# TemperatureSensor.net
KiCad netlist of a schematic drawn in EAGLE
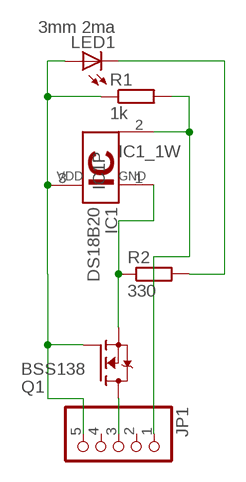
[diagram p0: schematic, sheet 1]

(export (version "E")
  (design (tool "Eeschema 10.0.6"))
  (components
    (comp (ref "IC1")
      (value "DS18B20")
      (footprint "eagle-import:TO92-")
      (libsource (lib "eagle-import") (part "DS18B20"))
    )
    (comp (ref "JP1")
      (value "PINHD-1X5")
      (footprint "eagle-import:1X05")
      (libsource (lib "eagle-import") (part "PINHD-1X5"))
    )
    (comp (ref "LED1")
      (value "3mm 2ma")
      (footprint "eagle-import:LED3MM")
      (fields (field (name "MF") "VISHAY SEMICONDUCTOR"))
      (libsource (lib "eagle-import") (part "TLLY4400"))
    )
    (comp (ref "Q1")
      (value "BSS138")
      (footprint "eagle-import:SOT23")
      (fields (field (name "MF") "Fairchild"))
      (libsource (lib "eagle-import") (part "BSS138"))
    )
    (comp (ref "R1")
      (value "1k")
      (footprint "eagle-import:R1206")
      (libsource (lib "eagle-import") (part "R-EU_R1206"))
    )
    (comp (ref "R2")
      (value "330")
      (footprint "eagle-import:R1206")
      (libsource (lib "eagle-import") (part "R-EU_R1206"))
    )
  )
  (nets
    (net (code "1") (name "Net-(IC1B-GND)") (class "Default")
      (node (ref "IC1") (pin "1") (pinfunction "GND_1") (pintype "power_in"))
      (node (ref "Q1") (pin "2") (pinfunction "S_2") (pintype "passive"))
      (node (ref "R2") (pin "1") (pinfunction "1_1") (pintype "passive"))
    )
    (net (code "2") (name "Net-(IC1B-VDD)") (class "Default")
      (node (ref "IC1") (pin "3") (pinfunction "VDD_3") (pintype "power_in"))
      (node (ref "JP1") (pin "5") (pinfunction "5_5") (pintype "passive"))
      (node (ref "LED1") (pin "A") (pinfunction "A_A") (pintype "passive"))
      (node (ref "Q1") (pin "1") (pinfunction "G_1") (pintype "passive"))
      (node (ref "R1") (pin "1") (pinfunction "1_1") (pintype "passive"))
    )
    (net (code "3") (name "Net-(IC1C-1W)") (class "Default")
      (node (ref "IC1") (pin "2") (pinfunction "1W_2") (pintype "power_in"))
      (node (ref "JP1") (pin "1") (pinfunction "1_1") (pintype "passive"))
      (node (ref "R1") (pin "2") (pinfunction "2_2") (pintype "passive"))
    )
    (net (code "4") (name "Net-(LED1-C)") (class "Default")
      (node (ref "LED1") (pin "K") (pinfunction "C_K") (pintype "passive"))
      (node (ref "R2") (pin "2") (pinfunction "2_2") (pintype "passive"))
    )
    (net (code "5") (name "Net-(Q1-D)") (class "Default")
      (node (ref "JP1") (pin "3") (pinfunction "3_3") (pintype "passive"))
      (node (ref "Q1") (pin "3") (pinfunction "D_3") (pintype "passive"))
    )
    (net (code "6") (name "unconnected-(JP1-Pad2)") (class "Default")
      (node (ref "JP1") (pin "2") (pinfunction "2_2") (pintype "passive"))
    )
    (net (code "7") (name "unconnected-(JP1-Pad4)") (class "Default")
      (node (ref "JP1") (pin "4") (pinfunction "4_4") (pintype "passive"))
    )
  )
)
